# LM2576_DC-DC_Converter.net
KiCad netlist of a schematic drawn in Altium Designer
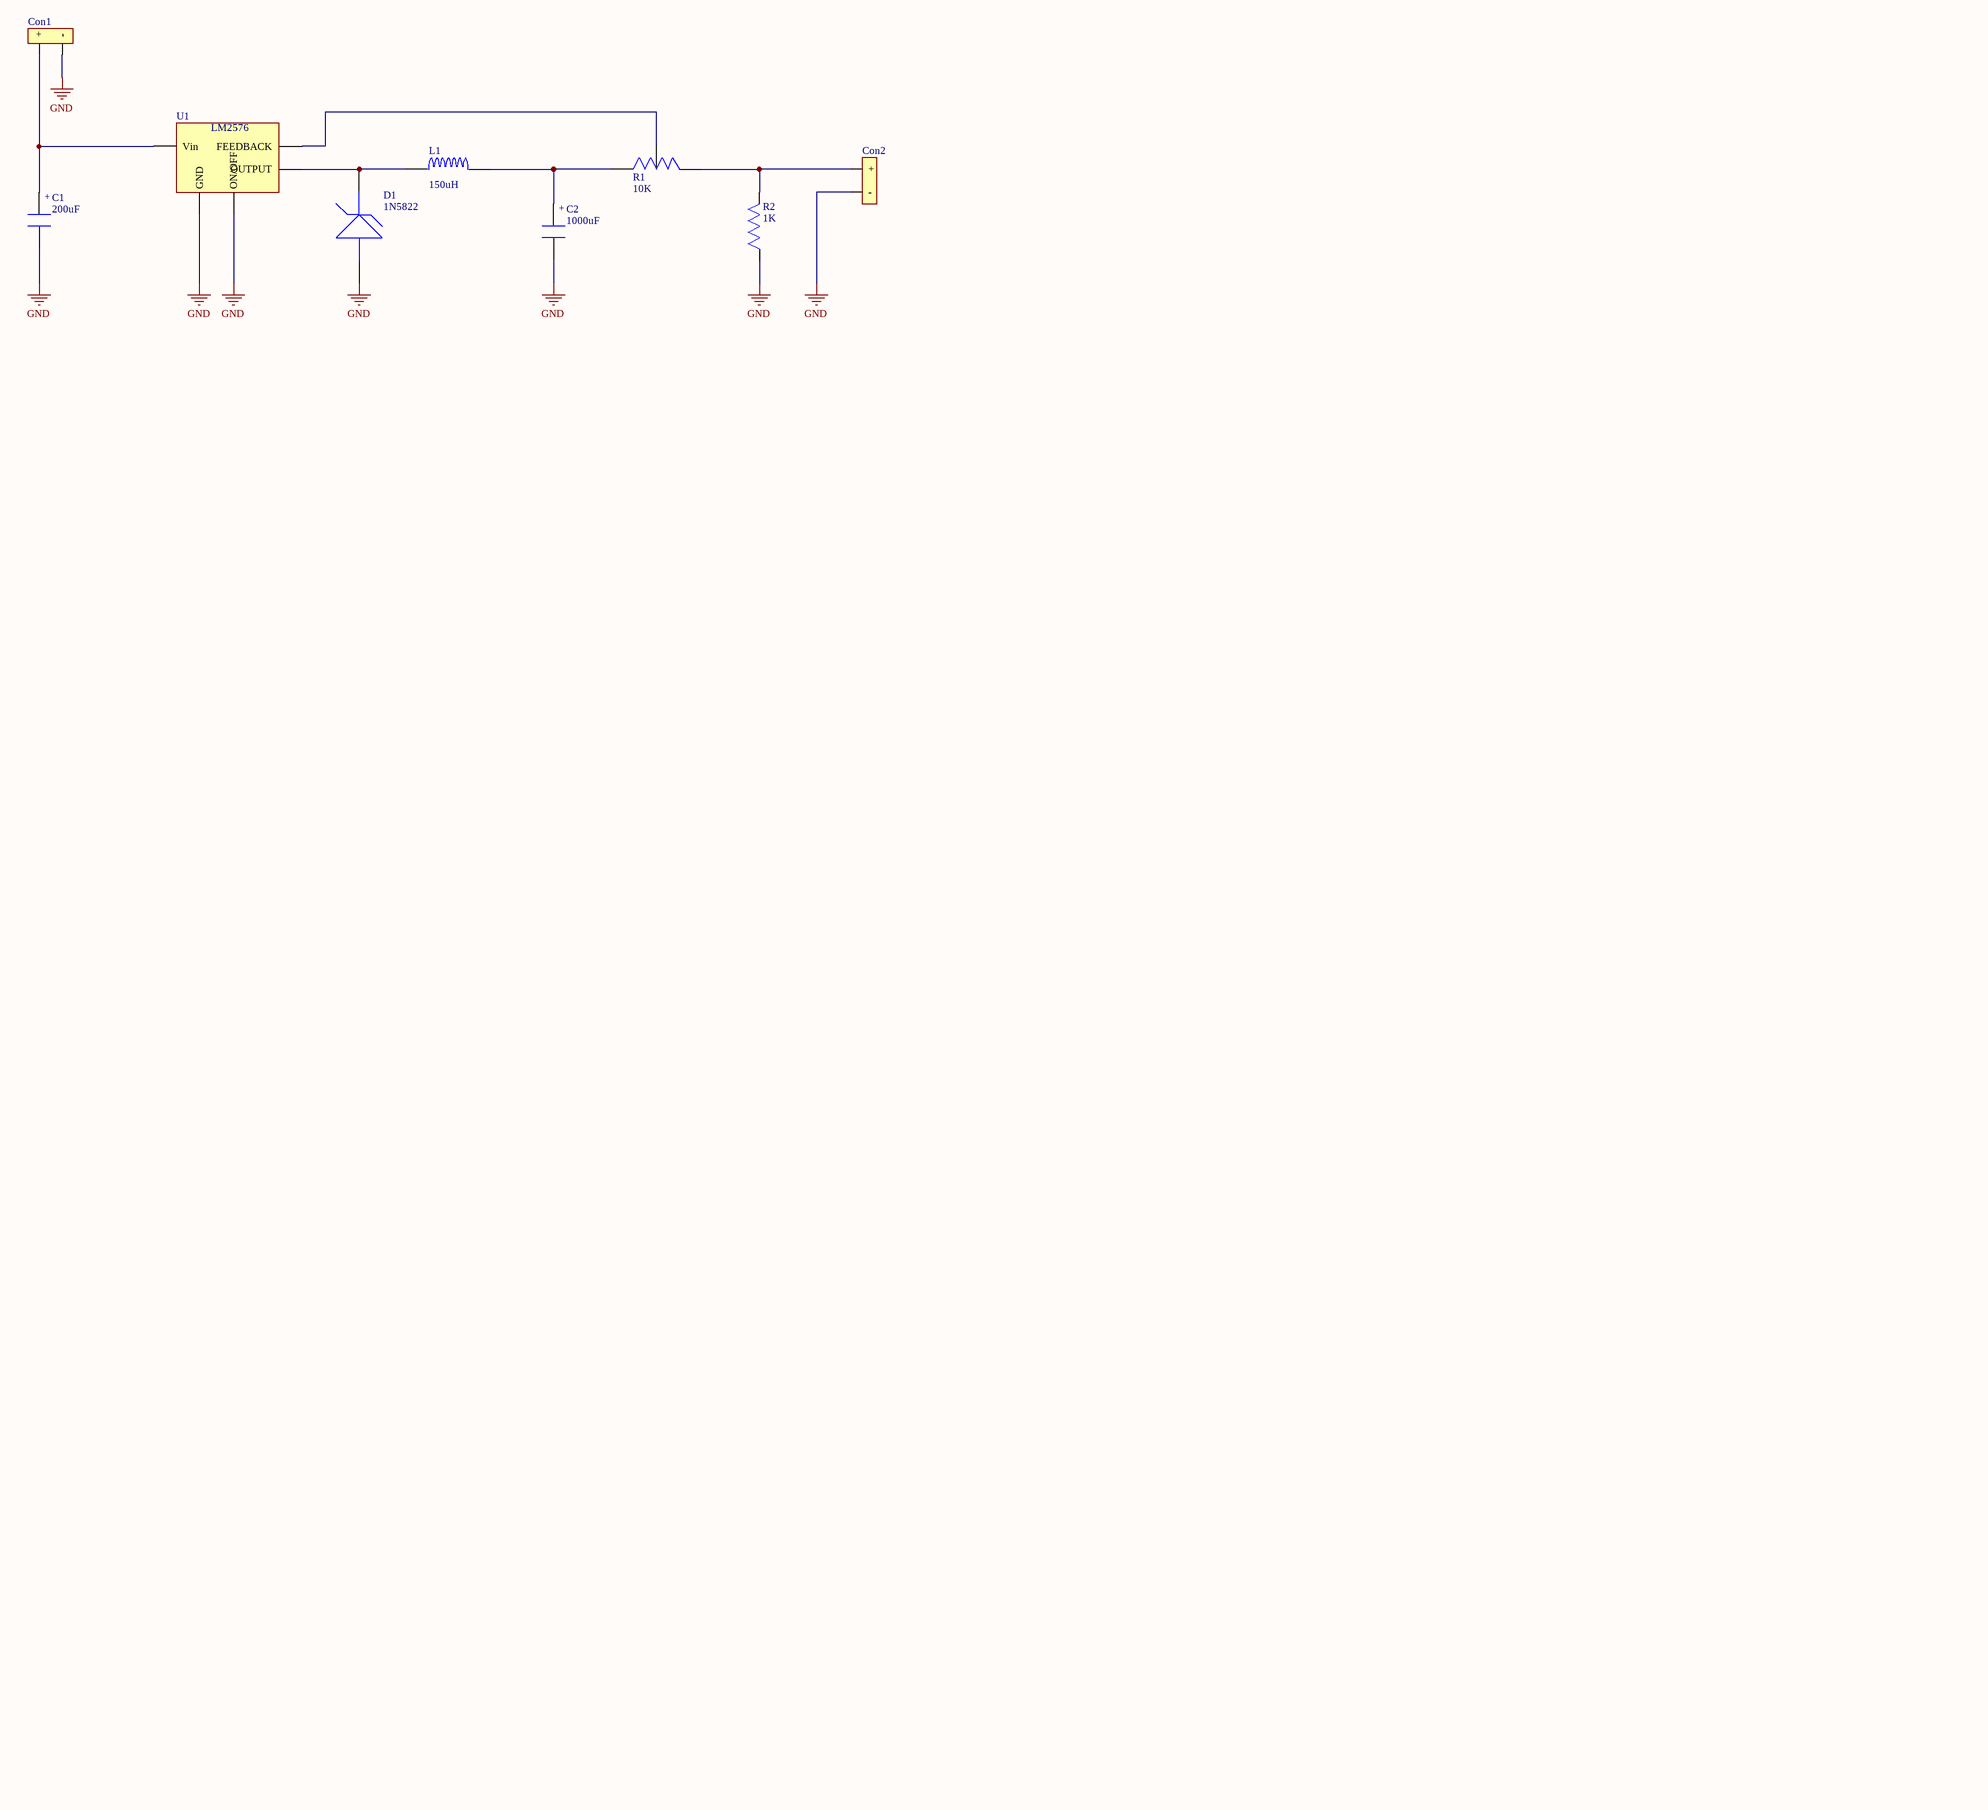
[diagram p0: LM2576_DC-DC_Converter.SchDoc]

(export (version "E")
  (design (tool "Eeschema 10.0.6"))
  (components
    (comp (ref "C1")
      (value "200uF")
      (footprint "220uF Capacitor")
      (description "Cap Aluminum 220uF 50V 20% (10 X 10mm) SMD 220mA 1000 hr 105°C T/R")
      (fields
        (field (name "MANUFACTURER") "Nichicon")
        (field (name "MANUFACTURER PART NUMBER") "UWT1H221MNL1GS")
      )
      (libsource (lib "LM2576_BuckConverter") (part "Electrolytic Cap 220uF"))
    )
    (comp (ref "C2")
      (value "1000uF")
      (footprint "1000Uf Cap")
      (description "CAP ALUM 1000UF 20% 50V SMD")
      (fields
        (field (name "MANUFACTURER") "Vishay BCcomponents")
        (field (name "MANUFACTURER PART NUMBER") "MAL214699111E3")
      )
      (libsource (lib "LM2576_BuckConverter") (part "Electrolytic Cap_1000uF"))
    )
    (comp (ref "Con1")
      (value "2pinconnector")
      (footprint "2pin")
      (description "Conn Unshrouded Header HDR 2 POS 2.54mm Solder ST Thru-Hole KK® Bag")
      (fields (field (name "MANUFACTURER") "Molex") (field (name "MANUFACTURER PART NUMBER") "22-10-2021"))
      (libsource (lib "") (part "2pinconnector_1"))
    )
    (comp (ref "Con2")
      (value "2pinconnector")
      (footprint "2pin")
      (description "Conn Unshrouded Header HDR 2 POS 2.54mm Solder ST Thru-Hole KK® Bag")
      (fields (field (name "MANUFACTURER") "Molex") (field (name "MANUFACTURER PART NUMBER") "22-10-2021"))
      (libsource (lib "LM2576_BuckConverter") (part "2pinconnector"))
    )
    (comp (ref "D1")
      (value "1N5822")
      (footprint "1n5822")
      (description "DIODE SCHOTTKY 40V 3A DO214AC")
      (fields (field (name "MANUFACTURER") "MCC") (field (name "MANUFACTURER PART NUMBER") "SK34A-LTP"))
      (libsource (lib "LM2576_BuckConverter") (part "1N5822"))
    )
    (comp (ref "L1")
      (value "150uH")
      (footprint "150uH Inductor")
      (fields
        (field (name "MANUFACTURER") "Wurth Electronics")
        (field (name "MANUFACTURER PART NUMBER") "7447706151")
      )
      (libsource (lib "LM2576_BuckConverter") (part "150uH L"))
    )
    (comp (ref "R1")
      (value "10K")
      (footprint "10K Pot")
      (fields
        (field (name "MANUFACTURER") "Bourns")
        (field (name "MANUFACTURER PART NUMBER") "3296W-1-103RLF")
        (field (name "TOLERANCE") "10%")
      )
      (libsource (lib "LM2576_BuckConverter") (part "Variable Resistor"))
    )
    (comp (ref "R2")
      (value "1K")
      (footprint "1K 1206 Res")
      (description "RES SMD 1K OHM 5% 1/4W 1206")
      (fields
        (field (name "MANUFACTURER") "Yageo")
        (field (name "MANUFACTURER PART NUMBER") "RC1206JR-071KL")
      )
      (libsource (lib "LM2576_BuckConverter") (part "Resistor"))
    )
    (comp (ref "U1")
      (value "LM2576")
      (footprint "LM2576-TO63-5")
      (description "Conv DC-DC Single Inv/Step Down 4V to 60V 6-Pin(5+Tab) TO-263 T/R")
      (fields
        (field (name "MANUFACTURER") "TI National Semiconductor")
        (field (name "MANUFACTURER PART NUMBER") "LM2576HVSX-ADJ/NOPB")
      )
      (libsource (lib "LM2576_BuckConverter") (part "LM2576"))
    )
  )
  (nets
    (net (code "1") (name "GND") (class "Default")
      (node (ref "C1") (pin "2") (pinfunction "2_2") (pintype "passive"))
      (node (ref "C2") (pin "2") (pinfunction "2_2") (pintype "passive"))
      (node (ref "Con1") (pin "2") (pinfunction "-_2") (pintype "passive"))
      (node (ref "Con2") (pin "2") (pinfunction "-_2") (pintype "passive"))
      (node (ref "D1") (pin "2") (pinfunction "2_2") (pintype "passive"))
      (node (ref "R2") (pin "1") (pinfunction "1_1") (pintype "passive"))
      (node (ref "U1") (pin "3") (pinfunction "GND_3") (pintype "passive"))
      (node (ref "U1") (pin "5") (pinfunction "ON/OFF_5") (pintype "passive"))
    )
    (net (code "2") (name "Net-(C2-Pad1)") (class "Default")
      (node (ref "C2") (pin "1") (pinfunction "1_1") (pintype "passive"))
      (node (ref "L1") (pin "2") (pinfunction "2_2") (pintype "passive"))
      (node (ref "R1") (pin "1") (pinfunction "1_1") (pintype "passive"))
    )
    (net (code "3") (name "Net-(Con1-+)") (class "Default")
      (node (ref "C1") (pin "1") (pinfunction "1_1") (pintype "passive"))
      (node (ref "Con1") (pin "1") (pinfunction "+_1") (pintype "passive"))
      (node (ref "U1") (pin "1") (pinfunction "Vin_1") (pintype "passive"))
    )
    (net (code "4") (name "Net-(Con2-+)") (class "Default")
      (node (ref "Con2") (pin "1") (pinfunction "+_1") (pintype "passive"))
      (node (ref "R1") (pin "3") (pinfunction "3_3") (pintype "passive"))
      (node (ref "R2") (pin "2") (pinfunction "2_2") (pintype "passive"))
    )
    (net (code "5") (name "Net-(U1-FEEDBACK)") (class "Default")
      (node (ref "R1") (pin "2") (pinfunction "2_2") (pintype "passive"))
      (node (ref "U1") (pin "4") (pinfunction "FEEDBACK_4") (pintype "passive"))
    )
    (net (code "6") (name "Net-(U1-OUTPUT)") (class "Default")
      (node (ref "D1") (pin "1") (pinfunction "1_1") (pintype "passive"))
      (node (ref "L1") (pin "1") (pinfunction "1_1") (pintype "passive"))
      (node (ref "U1") (pin "2") (pinfunction "OUTPUT_2") (pintype "passive"))
    )
  )
)
